# BedLevelSensor.net
KiCad netlist of a schematic drawn in EAGLE
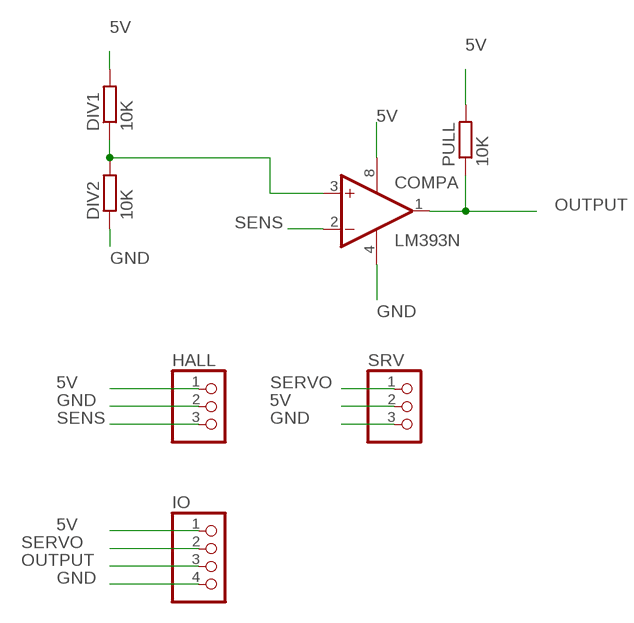
[diagram p0: schematic, sheet 1]

(export (version "E")
  (design (tool "Eeschema 10.0.6"))
  (components
    (comp (ref "COMP")
      (value "LM393N")
      (footprint "eagle-import:DIL08")
      (libsource (lib "eagle-import") (part "LM393N"))
    )
    (comp (ref "DIV1")
      (value "10K")
      (footprint "eagle-import:0204_5")
      (libsource (lib "eagle-import") (part "R-EU_0204/5"))
    )
    (comp (ref "DIV2")
      (value "10K")
      (footprint "eagle-import:0204_5")
      (libsource (lib "eagle-import") (part "R-EU_0204/5"))
    )
    (comp (ref "HALL")
      (value "PINHD-1X3")
      (footprint "eagle-import:1X03")
      (libsource (lib "eagle-import") (part "PINHD-1X3"))
    )
    (comp (ref "IO")
      (value "PINHD-1X4")
      (footprint "eagle-import:1X04")
      (libsource (lib "eagle-import") (part "PINHD-1X4"))
    )
    (comp (ref "PULL")
      (value "10K")
      (footprint "eagle-import:0204_5")
      (libsource (lib "eagle-import") (part "R-EU_0204/5"))
    )
    (comp (ref "SRV")
      (value "PINHD-1X3")
      (footprint "eagle-import:1X03")
      (libsource (lib "eagle-import") (part "PINHD-1X3"))
    )
  )
  (nets
    (net (code "1") (name "/5V") (class "Default")
      (node (ref "COMP") (pin "8") (pinfunction "V+_8") (pintype "power_in"))
      (node (ref "DIV1") (pin "2") (pinfunction "2_2") (pintype "passive"))
      (node (ref "HALL") (pin "1") (pinfunction "1_1") (pintype "passive"))
      (node (ref "IO") (pin "1") (pinfunction "1_1") (pintype "passive"))
      (node (ref "PULL") (pin "2") (pinfunction "2_2") (pintype "passive"))
      (node (ref "SRV") (pin "2") (pinfunction "2_2") (pintype "passive"))
    )
    (net (code "2") (name "/GND") (class "Default")
      (node (ref "COMP") (pin "4") (pinfunction "V-_4") (pintype "power_in"))
      (node (ref "DIV2") (pin "1") (pinfunction "1_1") (pintype "passive"))
      (node (ref "HALL") (pin "2") (pinfunction "2_2") (pintype "passive"))
      (node (ref "IO") (pin "4") (pinfunction "4_4") (pintype "passive"))
      (node (ref "SRV") (pin "3") (pinfunction "3_3") (pintype "passive"))
    )
    (net (code "3") (name "/OUTPUT") (class "Default")
      (node (ref "COMP") (pin "1") (pinfunction "OUT_1") (pintype "output"))
      (node (ref "IO") (pin "3") (pinfunction "3_3") (pintype "passive"))
      (node (ref "PULL") (pin "1") (pinfunction "1_1") (pintype "passive"))
    )
    (net (code "4") (name "/SENS") (class "Default")
      (node (ref "COMP") (pin "2") (pinfunction "-IN_2") (pintype "input"))
      (node (ref "HALL") (pin "3") (pinfunction "3_3") (pintype "passive"))
    )
    (net (code "5") (name "/SERVO") (class "Default")
      (node (ref "IO") (pin "2") (pinfunction "2_2") (pintype "passive"))
      (node (ref "SRV") (pin "1") (pinfunction "1_1") (pintype "passive"))
    )
    (net (code "6") (name "Net-(COMPA-+IN)") (class "Default")
      (node (ref "COMP") (pin "3") (pinfunction "+IN_3") (pintype "input"))
      (node (ref "DIV1") (pin "1") (pinfunction "1_1") (pintype "passive"))
      (node (ref "DIV2") (pin "2") (pinfunction "2_2") (pintype "passive"))
    )
  )
)
